# Sin_wave.net
KiCad netlist of a schematic drawn in Altium Designer
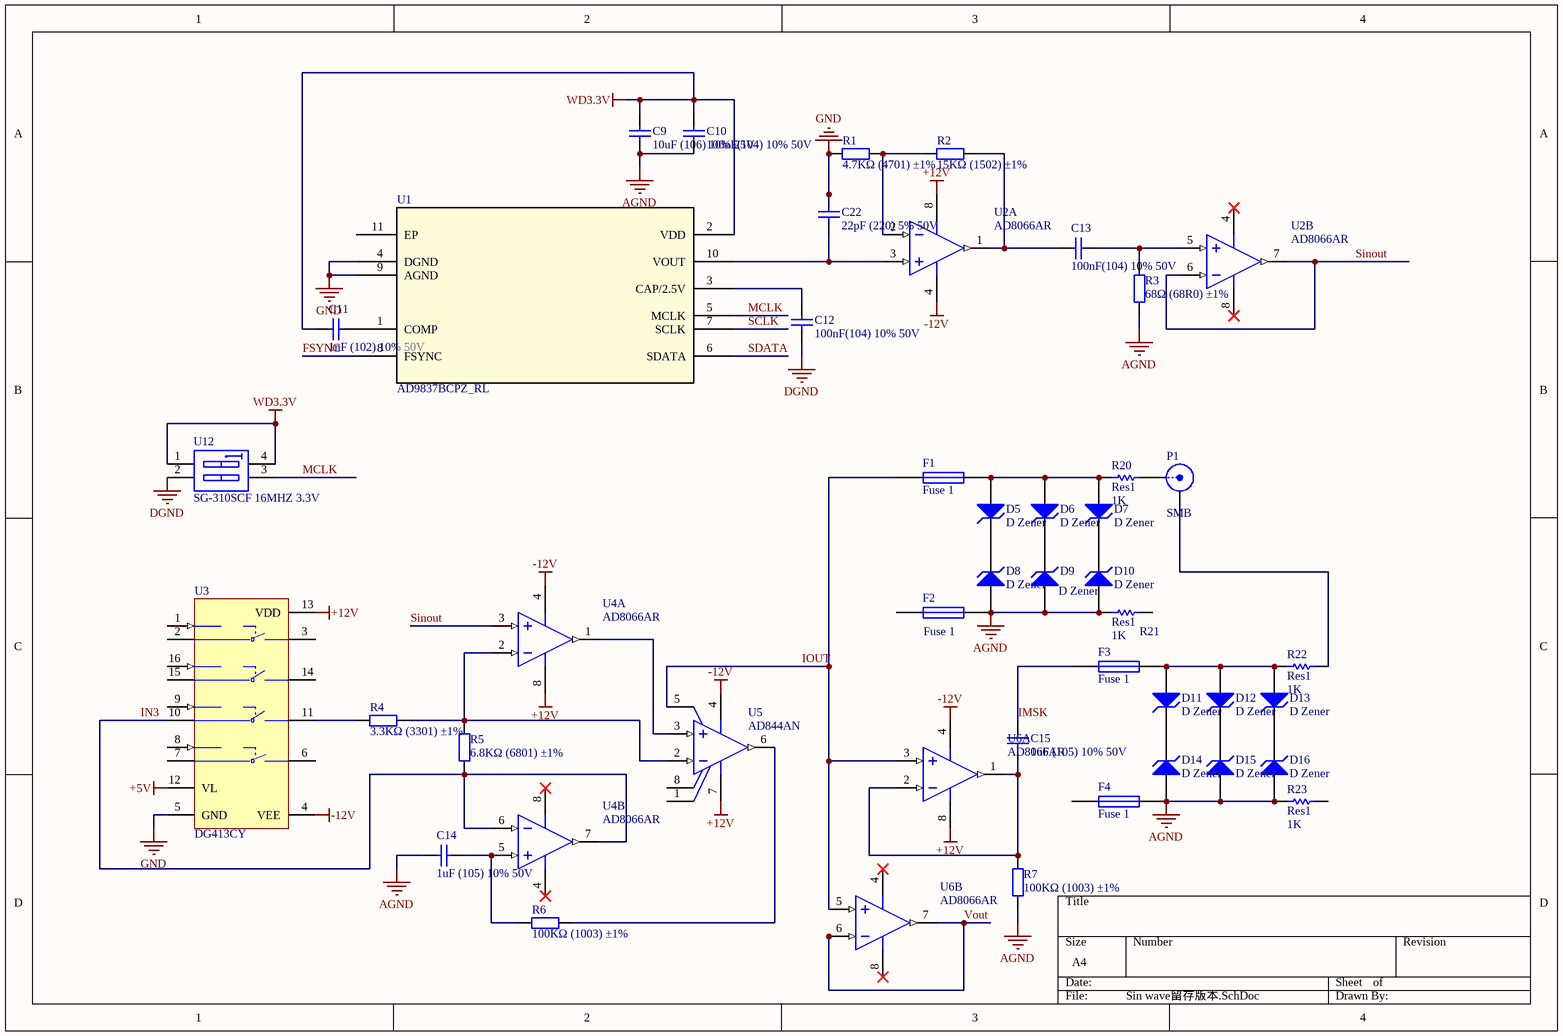
[diagram p0: Sin wave留存版本.SchDoc]

(export (version "E")
  (design (tool "Eeschema 10.0.6"))
  (components
    (comp (ref "C9")
      (value "10uF (106) 10% 25V")
      (footprint "LC-0805_C")
      (description "贴片电容")
      (libsource (lib "Miscellaneous Devices LC") (part "0805 10uF (106) 10% 25V"))
    )
    (comp (ref "C10")
      (value "100nF(104) 10% 50V")
      (footprint "LC-0805_C")
      (description "贴片电容")
      (libsource (lib "Miscellaneous Devices LC") (part "0805 100nF(104) 10% 50V"))
    )
    (comp (ref "C11")
      (value "1nF (102) 10% 50V")
      (footprint "LC-0805_C")
      (description "贴片电容")
      (libsource (lib "Miscellaneous Devices LC") (part "0805 1nF (102) 10% 50V"))
    )
    (comp (ref "C12")
      (value "100nF(104) 10% 50V")
      (footprint "LC-0805_C")
      (description "贴片电容")
      (libsource (lib "Miscellaneous Devices LC") (part "0805 100nF(104) 10% 50V"))
    )
    (comp (ref "C13")
      (value "100nF(104) 10% 50V")
      (footprint "LC-0805_C")
      (description "贴片电容")
      (libsource (lib "Miscellaneous Devices LC") (part "0805 100nF(104) 10% 50V"))
    )
    (comp (ref "C14")
      (value "1uF (105) 10% 50V")
      (footprint "LC-0805_C")
      (description "贴片电容")
      (libsource (lib "Miscellaneous Devices LC") (part "0805 1uF (105) 10% 50V"))
    )
    (comp (ref "C15")
      (value "1uF (105) 10% 50V")
      (footprint "LC-0805_C")
      (description "贴片电容")
      (libsource (lib "Miscellaneous Devices LC") (part "0805 1uF (105) 10% 50V"))
    )
    (comp (ref "C22")
      (value "22pF (220) 5% 50V")
      (footprint "LC-0805_C")
      (description "贴片电容")
      (libsource (lib "Miscellaneous Devices LC") (part "0805 22pF (220) 5% 50V"))
    )
    (comp (ref "D5")
      (value "D Zener")
      (footprint "DIODE-0.7")
      (description "Zener Diode")
      (fields (field (name "PUBLISHER") "Altium Limited"))
      (libsource (lib "Miscellaneous Devices") (part "D Zener"))
    )
    (comp (ref "D6")
      (value "D Zener")
      (footprint "DIODE-0.7")
      (description "Zener Diode")
      (fields (field (name "PUBLISHER") "Altium Limited"))
      (libsource (lib "Miscellaneous Devices") (part "D Zener"))
    )
    (comp (ref "D7")
      (value "D Zener")
      (footprint "DIODE-0.7")
      (description "Zener Diode")
      (fields (field (name "PUBLISHER") "Altium Limited"))
      (libsource (lib "Miscellaneous Devices") (part "D Zener"))
    )
    (comp (ref "D8")
      (value "D Zener")
      (footprint "DIODE-0.7")
      (description "Zener Diode")
      (fields (field (name "PUBLISHER") "Altium Limited"))
      (libsource (lib "Miscellaneous Devices") (part "D Zener"))
    )
    (comp (ref "D9")
      (value "D Zener")
      (footprint "DIODE-0.7")
      (description "Zener Diode")
      (fields (field (name "PUBLISHER") "Altium Limited"))
      (libsource (lib "Miscellaneous Devices") (part "D Zener"))
    )
    (comp (ref "D10")
      (value "D Zener")
      (footprint "DIODE-0.7")
      (description "Zener Diode")
      (fields (field (name "PUBLISHER") "Altium Limited"))
      (libsource (lib "Miscellaneous Devices") (part "D Zener"))
    )
    (comp (ref "D11")
      (value "D Zener")
      (footprint "DIODE-0.7")
      (description "Zener Diode")
      (fields (field (name "PUBLISHER") "Altium Limited"))
      (libsource (lib "Miscellaneous Devices") (part "D Zener"))
    )
    (comp (ref "D12")
      (value "D Zener")
      (footprint "DIODE-0.7")
      (description "Zener Diode")
      (fields (field (name "PUBLISHER") "Altium Limited"))
      (libsource (lib "Miscellaneous Devices") (part "D Zener"))
    )
    (comp (ref "D13")
      (value "D Zener")
      (footprint "DIODE-0.7")
      (description "Zener Diode")
      (fields (field (name "PUBLISHER") "Altium Limited"))
      (libsource (lib "Miscellaneous Devices") (part "D Zener"))
    )
    (comp (ref "D14")
      (value "D Zener")
      (footprint "DIODE-0.7")
      (description "Zener Diode")
      (fields (field (name "PUBLISHER") "Altium Limited"))
      (libsource (lib "Miscellaneous Devices") (part "D Zener"))
    )
    (comp (ref "D15")
      (value "D Zener")
      (footprint "DIODE-0.7")
      (description "Zener Diode")
      (fields (field (name "PUBLISHER") "Altium Limited"))
      (libsource (lib "Miscellaneous Devices") (part "D Zener"))
    )
    (comp (ref "D16")
      (value "D Zener")
      (footprint "DIODE-0.7")
      (description "Zener Diode")
      (fields (field (name "PUBLISHER") "Altium Limited"))
      (libsource (lib "Miscellaneous Devices") (part "D Zener"))
    )
    (comp (ref "F1")
      (value "Fuse 1")
      (footprint "PIN-W2/E2.8")
      (description "Fuse")
      (fields (field (name "PUBLISHER") "Altium Limited"))
      (libsource (lib "Miscellaneous Devices") (part "Fuse 1"))
    )
    (comp (ref "F2")
      (value "Fuse 1")
      (footprint "PIN-W2/E2.8")
      (description "Fuse")
      (fields (field (name "PUBLISHER") "Altium Limited"))
      (libsource (lib "Miscellaneous Devices") (part "Fuse 1"))
    )
    (comp (ref "F3")
      (value "Fuse 1")
      (footprint "PIN-W2/E2.8")
      (description "Fuse")
      (fields (field (name "PUBLISHER") "Altium Limited"))
      (libsource (lib "Miscellaneous Devices") (part "Fuse 1"))
    )
    (comp (ref "F4")
      (value "Fuse 1")
      (footprint "PIN-W2/E2.8")
      (description "Fuse")
      (fields (field (name "PUBLISHER") "Altium Limited"))
      (libsource (lib "Miscellaneous Devices") (part "Fuse 1"))
    )
    (comp (ref "P1")
      (value "SMB")
      (footprint "SMB_V-RJ45")
      (description "SMB Straight Connector")
      (fields (field (name "PUBLISHER") "Altium Limited"))
      (libsource (lib "Miscellaneous Connectors") (part "SMB"))
    )
    (comp (ref "R1")
      (value "4.7KΩ (4701) ±1%")
      (footprint "LC-0805_R")
      (description "贴片电阻")
      (libsource (lib "Miscellaneous Devices LC") (part "0805 4.7KΩ (4701) 1%"))
    )
    (comp (ref "R2")
      (value "15KΩ (1502) ±1%")
      (footprint "LC-0805_R")
      (description "贴片电阻")
      (libsource (lib "Miscellaneous Devices LC") (part "0805 15KΩ (1502) 1%"))
    )
    (comp (ref "R3")
      (value "68Ω (68R0) ±1%")
      (footprint "LC-0805_R")
      (description "贴片电阻")
      (libsource (lib "Miscellaneous Devices LC") (part "0805 68Ω (68R0) 1%"))
    )
    (comp (ref "R4")
      (value "3.3KΩ (3301) ±1%")
      (footprint "LC-0805_R")
      (description "贴片电阻")
      (libsource (lib "Miscellaneous Devices LC") (part "0805 3.3KΩ (3301) 1%"))
    )
    (comp (ref "R5")
      (value "6.8KΩ (6801) ±1%")
      (footprint "LC-0805_R")
      (description "贴片电阻")
      (libsource (lib "Miscellaneous Devices LC") (part "0805 6.8KΩ (6801) 1%"))
    )
    (comp (ref "R6")
      (value "100KΩ (1003) ±1%")
      (footprint "LC-0805_R")
      (description "贴片电阻")
      (libsource (lib "Miscellaneous Devices LC") (part "0805 100KΩ (1003) 1%"))
    )
    (comp (ref "R7")
      (value "100KΩ (1003) ±1%")
      (footprint "LC-0805_R")
      (description "贴片电阻")
      (libsource (lib "") (part "0805 100KΩ (1003) 1%_1"))
    )
    (comp (ref "R20")
      (value "Res1")
      (footprint "AXIAL-0.3")
      (description "Resistor")
      (fields (field (name "ALTIUM_VALUE") "1K") (field (name "PUBLISHER") "Altium Limited"))
      (libsource (lib "Miscellaneous Devices") (part "Res1"))
    )
    (comp (ref "R21")
      (value "Res1")
      (footprint "AXIAL-0.3")
      (description "Resistor")
      (fields (field (name "ALTIUM_VALUE") "1K") (field (name "PUBLISHER") "Altium Limited"))
      (libsource (lib "Miscellaneous Devices") (part "Res1"))
    )
    (comp (ref "R22")
      (value "Res1")
      (footprint "AXIAL-0.3")
      (description "Resistor")
      (fields (field (name "ALTIUM_VALUE") "1K") (field (name "PUBLISHER") "Altium Limited"))
      (libsource (lib "Miscellaneous Devices") (part "Res1"))
    )
    (comp (ref "R23")
      (value "Res1")
      (footprint "AXIAL-0.3")
      (description "Resistor")
      (fields (field (name "ALTIUM_VALUE") "1K") (field (name "PUBLISHER") "Altium Limited"))
      (libsource (lib "Miscellaneous Devices") (part "Res1"))
    )
    (comp (ref "U1")
      (value "AD9837BCPZ_RL")
      (footprint "CP_10_9")
      (description "Imported")
      (libsource (lib "AD9837") (part "AD9837BCPZ_RL"))
    )
    (comp (ref "U2")
      (value "AD8066AR")
      (footprint "ADI-R-8_N")
      (fields (field (name "GENERIC PART NUMBER") "AD8066") (field (name "MANUFACTURER") "Analog Devices"))
      (libsource (lib "Analog Devices Operational Amplifiers") (part "AD8066AR"))
    )
    (comp (ref "U3")
      (value "DG413CY")
      (footprint "NSO16_N")
      (description "Improved, Quad, SPST Analog Switches")
      (fields (field (name "PUBLISHER") "Altium Limited"))
      (libsource (lib "Maxim Logic Switch") (part "DG413CY"))
    )
    (comp (ref "U4")
      (value "AD8066AR")
      (footprint "ADI-R-8_N")
      (fields (field (name "GENERIC PART NUMBER") "AD8066") (field (name "MANUFACTURER") "Analog Devices"))
      (libsource (lib "Analog Devices Operational Amplifiers") (part "AD8066AR"))
    )
    (comp (ref "U5")
      (value "AD844AN")
      (footprint "ADI-N-8")
      (fields (field (name "GENERIC PART NUMBER") "AD844") (field (name "MANUFACTURER") "Analog Devices"))
      (libsource (lib "Analog Devices Operational Amplifiers") (part "AD844AN"))
    )
    (comp (ref "U6")
      (value "AD8066AR")
      (footprint "ADI-R-8_N")
      (fields (field (name "GENERIC PART NUMBER") "AD8066") (field (name "MANUFACTURER") "Analog Devices"))
      (libsource (lib "Analog Devices Operational Amplifiers") (part "AD8066AR"))
    )
    (comp (ref "U12")
      (value "SG-310SCF 16MHZ 3.3V")
      (footprint "LC-SMD-7050_4P")
      (description "DIP Switch, 2 Position, SPST")
      (fields (field (name "PUBLISHER") "Altium Limited"))
      (libsource (lib "Miscellaneous Devices") (part "SW DIP-2"))
    )
  )
  (nets
    (net (code "1") (name "+5V") (class "Default")
      (node (ref "U3") (pin "12") (pinfunction "VL_12") (pintype "power_in"))
    )
    (net (code "2") (name "+12V") (class "Default")
      (node (ref "U2") (pin "8") (pinfunction "+VS_8") (pintype "power_in"))
      (node (ref "U3") (pin "13") (pinfunction "VDD_13") (pintype "power_in"))
      (node (ref "U4") (pin "8") (pinfunction "+VS_8") (pintype "power_in"))
      (node (ref "U5") (pin "7") (pinfunction "+VS_7") (pintype "power_in"))
      (node (ref "U6") (pin "8") (pinfunction "+VS_8") (pintype "power_in"))
    )
    (net (code "3") (name "-12V") (class "Default")
      (node (ref "U2") (pin "4") (pinfunction "-VS_4") (pintype "power_in"))
      (node (ref "U3") (pin "4") (pinfunction "VEE_4") (pintype "power_in"))
      (node (ref "U4") (pin "4") (pinfunction "-VS_4") (pintype "power_in"))
      (node (ref "U5") (pin "4") (pinfunction "-VS_4") (pintype "power_in"))
      (node (ref "U6") (pin "4") (pinfunction "-VS_4") (pintype "power_in"))
    )
    (net (code "4") (name "/FSYNC") (class "Default")
      (node (ref "U1") (pin "8") (pinfunction "FSYNC_8") (pintype "passive"))
    )
    (net (code "5") (name "/IMSK") (class "Default")
      (node (ref "C15") (pin "2") (pinfunction "2_2") (pintype "passive"))
      (node (ref "F3") (pin "1") (pinfunction "1_1") (pintype "passive"))
    )
    (net (code "6") (name "/IN3") (class "Default")
      (node (ref "R5") (pin "1") (pinfunction "1_1") (pintype "passive"))
      (node (ref "U3") (pin "10") (pinfunction "D3_10") (pintype "passive"))
      (node (ref "U4") (pin "6") (pinfunction "-IN_2_6") (pintype "input"))
      (node (ref "U4") (pin "7") (pinfunction "VOUT_2_7") (pintype "output"))
    )
    (net (code "7") (name "/IOUT") (class "Default")
      (node (ref "F1") (pin "1") (pinfunction "1_1") (pintype "passive"))
      (node (ref "U5") (pin "5") (pinfunction "TZ_5") (pintype "passive"))
      (node (ref "U6") (pin "3") (pinfunction "+IN_1_3") (pintype "input"))
      (node (ref "U6") (pin "5") (pinfunction "+IN_2_5") (pintype "input"))
    )
    (net (code "8") (name "/MCLK") (class "Default")
      (node (ref "U1") (pin "5") (pinfunction "MCLK_5") (pintype "passive"))
      (node (ref "U12") (pin "3") (pinfunction "B2_3") (pintype "passive"))
    )
    (net (code "9") (name "/SCLK") (class "Default")
      (node (ref "U1") (pin "7") (pinfunction "SCLK_7") (pintype "passive"))
    )
    (net (code "10") (name "/SDATA") (class "Default")
      (node (ref "U1") (pin "6") (pinfunction "SDATA_6") (pintype "passive"))
    )
    (net (code "11") (name "/Sinout") (class "Default")
      (node (ref "U2") (pin "6") (pinfunction "-IN_2_6") (pintype "input"))
      (node (ref "U2") (pin "7") (pinfunction "VOUT_2_7") (pintype "output"))
      (node (ref "U4") (pin "3") (pinfunction "+IN_1_3") (pintype "input"))
    )
    (net (code "12") (name "/Vout") (class "Default")
      (node (ref "U6") (pin "6") (pinfunction "-IN_2_6") (pintype "input"))
      (node (ref "U6") (pin "7") (pinfunction "VOUT_2_7") (pintype "output"))
    )
    (net (code "13") (name "AGND") (class "Default")
      (node (ref "C10") (pin "1") (pinfunction "1_1") (pintype "passive"))
      (node (ref "C14") (pin "1") (pinfunction "1_1") (pintype "passive"))
      (node (ref "C9") (pin "1") (pinfunction "1_1") (pintype "passive"))
      (node (ref "D10") (pin "1") (pinfunction "A_1") (pintype "passive"))
      (node (ref "D14") (pin "1") (pinfunction "A_1") (pintype "passive"))
      (node (ref "D15") (pin "1") (pinfunction "A_1") (pintype "passive"))
      (node (ref "D16") (pin "1") (pinfunction "A_1") (pintype "passive"))
      (node (ref "D8") (pin "1") (pinfunction "A_1") (pintype "passive"))
      (node (ref "D9") (pin "1") (pinfunction "A_1") (pintype "passive"))
      (node (ref "F2") (pin "2") (pinfunction "2_2") (pintype "passive"))
      (node (ref "F4") (pin "2") (pinfunction "2_2") (pintype "passive"))
      (node (ref "R21") (pin "1") (pinfunction "1_1") (pintype "passive"))
      (node (ref "R23") (pin "1") (pinfunction "1_1") (pintype "passive"))
      (node (ref "R3") (pin "1") (pinfunction "1_1") (pintype "passive"))
      (node (ref "R7") (pin "1") (pinfunction "1_1") (pintype "passive"))
    )
    (net (code "14") (name "DGND") (class "Default")
      (node (ref "C12") (pin "1") (pinfunction "1_1") (pintype "passive"))
      (node (ref "U12") (pin "2") (pinfunction "A2_2") (pintype "passive"))
    )
    (net (code "15") (name "GND") (class "Default")
      (node (ref "C22") (pin "2") (pinfunction "2_2") (pintype "passive"))
      (node (ref "R1") (pin "1") (pinfunction "1_1") (pintype "passive"))
      (node (ref "U1") (pin "4") (pinfunction "DGND_4") (pintype "passive"))
      (node (ref "U1") (pin "9") (pinfunction "AGND_9") (pintype "passive"))
      (node (ref "U3") (pin "5") (pinfunction "GND_5") (pintype "power_in"))
    )
    (net (code "16") (name "Net-(D5-A)") (class "Default")
      (node (ref "D5") (pin "1") (pinfunction "A_1") (pintype "passive"))
      (node (ref "D6") (pin "1") (pinfunction "A_1") (pintype "passive"))
      (node (ref "D7") (pin "1") (pinfunction "A_1") (pintype "passive"))
      (node (ref "F1") (pin "2") (pinfunction "2_2") (pintype "passive"))
      (node (ref "R20") (pin "1") (pinfunction "1_1") (pintype "passive"))
    )
    (net (code "17") (name "Net-(D5-K)") (class "Default")
      (node (ref "D5") (pin "2") (pinfunction "K_2") (pintype "passive"))
      (node (ref "D8") (pin "2") (pinfunction "K_2") (pintype "passive"))
    )
    (net (code "18") (name "Net-(D6-K)") (class "Default")
      (node (ref "D6") (pin "2") (pinfunction "K_2") (pintype "passive"))
      (node (ref "D9") (pin "2") (pinfunction "K_2") (pintype "passive"))
    )
    (net (code "19") (name "Net-(D10-K)") (class "Default")
      (node (ref "D10") (pin "2") (pinfunction "K_2") (pintype "passive"))
      (node (ref "D7") (pin "2") (pinfunction "K_2") (pintype "passive"))
    )
    (net (code "20") (name "Net-(D11-A)") (class "Default")
      (node (ref "D11") (pin "1") (pinfunction "A_1") (pintype "passive"))
      (node (ref "D12") (pin "1") (pinfunction "A_1") (pintype "passive"))
      (node (ref "D13") (pin "1") (pinfunction "A_1") (pintype "passive"))
      (node (ref "F3") (pin "2") (pinfunction "2_2") (pintype "passive"))
      (node (ref "R22") (pin "1") (pinfunction "1_1") (pintype "passive"))
    )
    (net (code "21") (name "Net-(D11-K)") (class "Default")
      (node (ref "D11") (pin "2") (pinfunction "K_2") (pintype "passive"))
      (node (ref "D14") (pin "2") (pinfunction "K_2") (pintype "passive"))
    )
    (net (code "22") (name "Net-(D12-K)") (class "Default")
      (node (ref "D12") (pin "2") (pinfunction "K_2") (pintype "passive"))
      (node (ref "D15") (pin "2") (pinfunction "K_2") (pintype "passive"))
    )
    (net (code "23") (name "Net-(D13-K)") (class "Default")
      (node (ref "D13") (pin "2") (pinfunction "K_2") (pintype "passive"))
      (node (ref "D16") (pin "2") (pinfunction "K_2") (pintype "passive"))
    )
    (net (code "24") (name "Net-(P1-X)") (class "Default")
      (node (ref "P1") (pin "1") (pinfunction "X_1") (pintype "passive"))
      (node (ref "R20") (pin "2") (pinfunction "2_2") (pintype "passive"))
    )
    (net (code "25") (name "Net-(P1-Y)") (class "Default")
      (node (ref "P1") (pin "2") (pinfunction "Y_2") (pintype "passive"))
      (node (ref "R22") (pin "2") (pinfunction "2_2") (pintype "passive"))
    )
    (net (code "26") (name "Net-(U1-CAP{slash}2.5V)") (class "Default")
      (node (ref "C12") (pin "2") (pinfunction "2_2") (pintype "passive"))
      (node (ref "U1") (pin "3") (pinfunction "CAP/2.5V_3") (pintype "passive"))
    )
    (net (code "27") (name "Net-(U1-COMP)") (class "Default")
      (node (ref "C11") (pin "2") (pinfunction "2_2") (pintype "passive"))
      (node (ref "U1") (pin "1") (pinfunction "COMP_1") (pintype "passive"))
    )
    (net (code "28") (name "Net-(U1-VOUT)") (class "Default")
      (node (ref "C22") (pin "1") (pinfunction "1_1") (pintype "passive"))
      (node (ref "U1") (pin "10") (pinfunction "VOUT_10") (pintype "passive"))
      (node (ref "U2") (pin "3") (pinfunction "+IN_1_3") (pintype "input"))
    )
    (net (code "29") (name "Net-(U2A--IN_1)") (class "Default")
      (node (ref "R1") (pin "2") (pinfunction "2_2") (pintype "passive"))
      (node (ref "R2") (pin "1") (pinfunction "1_1") (pintype "passive"))
      (node (ref "U2") (pin "2") (pinfunction "-IN_1_2") (pintype "input"))
    )
    (net (code "30") (name "Net-(U2A-VOUT_1)") (class "Default")
      (node (ref "C13") (pin "1") (pinfunction "1_1") (pintype "passive"))
      (node (ref "R2") (pin "2") (pinfunction "2_2") (pintype "passive"))
      (node (ref "U2") (pin "1") (pinfunction "VOUT_1_1") (pintype "output"))
    )
    (net (code "31") (name "Net-(U2B-+IN_2)") (class "Default")
      (node (ref "C13") (pin "2") (pinfunction "2_2") (pintype "passive"))
      (node (ref "R3") (pin "2") (pinfunction "2_2") (pintype "passive"))
      (node (ref "U2") (pin "5") (pinfunction "+IN_2_5") (pintype "input"))
    )
    (net (code "32") (name "Net-(U3-S3)") (class "Default")
      (node (ref "R4") (pin "1") (pinfunction "1_1") (pintype "passive"))
      (node (ref "U3") (pin "11") (pinfunction "S3_11") (pintype "passive"))
    )
    (net (code "33") (name "Net-(U4A--IN_1)") (class "Default")
      (node (ref "R4") (pin "2") (pinfunction "2_2") (pintype "passive"))
      (node (ref "R5") (pin "2") (pinfunction "2_2") (pintype "passive"))
      (node (ref "U4") (pin "2") (pinfunction "-IN_1_2") (pintype "input"))
      (node (ref "U5") (pin "2") (pinfunction "-IN_2") (pintype "input"))
    )
    (net (code "34") (name "Net-(U4A-VOUT_1)") (class "Default")
      (node (ref "U4") (pin "1") (pinfunction "VOUT_1_1") (pintype "output"))
      (node (ref "U5") (pin "3") (pinfunction "+IN_3") (pintype "input"))
    )
    (net (code "35") (name "Net-(U4B-+IN_2)") (class "Default")
      (node (ref "C14") (pin "2") (pinfunction "2_2") (pintype "passive"))
      (node (ref "R6") (pin "1") (pinfunction "1_1") (pintype "passive"))
      (node (ref "U4") (pin "5") (pinfunction "+IN_2_5") (pintype "input"))
    )
    (net (code "36") (name "Net-(U5-OUTPUT)") (class "Default")
      (node (ref "R6") (pin "2") (pinfunction "2_2") (pintype "passive"))
      (node (ref "U5") (pin "6") (pinfunction "OUTPUT_6") (pintype "output"))
    )
    (net (code "37") (name "Net-(U6A--IN_1)") (class "Default")
      (node (ref "C15") (pin "1") (pinfunction "1_1") (pintype "passive"))
      (node (ref "R7") (pin "2") (pinfunction "2_2") (pintype "passive"))
      (node (ref "U6") (pin "1") (pinfunction "VOUT_1_1") (pintype "output"))
      (node (ref "U6") (pin "2") (pinfunction "-IN_1_2") (pintype "input"))
    )
    (net (code "38") (name "WD3.3V") (class "Default")
      (node (ref "C10") (pin "2") (pinfunction "2_2") (pintype "passive"))
      (node (ref "C11") (pin "1") (pinfunction "1_1") (pintype "passive"))
      (node (ref "C9") (pin "2") (pinfunction "2_2") (pintype "passive"))
      (node (ref "U1") (pin "2") (pinfunction "VDD_2") (pintype "passive"))
      (node (ref "U12") (pin "1") (pinfunction "A1_1") (pintype "passive"))
      (node (ref "U12") (pin "4") (pinfunction "B1_4") (pintype "passive"))
    )
    (net (code "39") (name "unconnected-(F2-Pad1)") (class "Default")
      (node (ref "F2") (pin "1") (pinfunction "1_1") (pintype "passive"))
    )
    (net (code "40") (name "unconnected-(F4-Pad1)") (class "Default")
      (node (ref "F4") (pin "1") (pinfunction "1_1") (pintype "passive"))
    )
    (net (code "41") (name "unconnected-(R21-Pad2)") (class "Default")
      (node (ref "R21") (pin "2") (pinfunction "2_2") (pintype "passive"))
    )
    (net (code "42") (name "unconnected-(R23-Pad2)") (class "Default")
      (node (ref "R23") (pin "2") (pinfunction "2_2") (pintype "passive"))
    )
    (net (code "43") (name "unconnected-(U1-EP-Pad11)") (class "Default")
      (node (ref "U1") (pin "11") (pinfunction "EP_11") (pintype "passive"))
    )
    (net (code "44") (name "unconnected-(U2B-+VS-Pad8)") (class "Default")
      (node (ref "U2") (pin "8") (pinfunction "+VS_8") (pintype "power_in+no_connect"))
    )
    (net (code "45") (name "unconnected-(U2B--VS-Pad4)") (class "Default")
      (node (ref "U2") (pin "4") (pinfunction "-VS_4") (pintype "power_in+no_connect"))
    )
    (net (code "46") (name "unconnected-(U3-D1-Pad2)") (class "Default")
      (node (ref "U3") (pin "2") (pinfunction "D1_2") (pintype "passive"))
    )
    (net (code "47") (name "unconnected-(U3-D2-Pad15)") (class "Default")
      (node (ref "U3") (pin "15") (pinfunction "D2_15") (pintype "passive"))
    )
    (net (code "48") (name "unconnected-(U3-D4-Pad7)") (class "Default")
      (node (ref "U3") (pin "7") (pinfunction "D4_7") (pintype "passive"))
    )
    (net (code "49") (name "unconnected-(U3-IN1-Pad1)") (class "Default")
      (node (ref "U3") (pin "1") (pinfunction "IN1_1") (pintype "input"))
    )
    (net (code "50") (name "unconnected-(U3-IN2-Pad16)") (class "Default")
      (node (ref "U3") (pin "16") (pinfunction "IN2_16") (pintype "input"))
    )
    (net (code "51") (name "unconnected-(U3-IN3-Pad9)") (class "Default")
      (node (ref "U3") (pin "9") (pinfunction "IN3_9") (pintype "input"))
    )
    (net (code "52") (name "unconnected-(U3-IN_4-Pad8)") (class "Default")
      (node (ref "U3") (pin "8") (pinfunction "IN_4_8") (pintype "input"))
    )
    (net (code "53") (name "unconnected-(U3-S1-Pad3)") (class "Default")
      (node (ref "U3") (pin "3") (pinfunction "S1_3") (pintype "passive"))
    )
    (net (code "54") (name "unconnected-(U3-S2-Pad14)") (class "Default")
      (node (ref "U3") (pin "14") (pinfunction "S2_14") (pintype "passive"))
    )
    (net (code "55") (name "unconnected-(U3-S4-Pad6)") (class "Default")
      (node (ref "U3") (pin "6") (pinfunction "S4_6") (pintype "passive"))
    )
    (net (code "56") (name "unconnected-(U4B-+VS-Pad8)") (class "Default")
      (node (ref "U4") (pin "8") (pinfunction "+VS_8") (pintype "power_in+no_connect"))
    )
    (net (code "57") (name "unconnected-(U4B--VS-Pad4)") (class "Default")
      (node (ref "U4") (pin "4") (pinfunction "-VS_4") (pintype "power_in+no_connect"))
    )
    (net (code "58") (name "unconnected-(U5-NULL-Pad1)") (class "Default")
      (node (ref "U5") (pin "1") (pinfunction "NULL_1") (pintype "passive"))
    )
    (net (code "59") (name "unconnected-(U5-NULL-Pad8)") (class "Default")
      (node (ref "U5") (pin "8") (pinfunction "NULL_8") (pintype "passive"))
    )
    (net (code "60") (name "unconnected-(U6B-+VS-Pad8)") (class "Default")
      (node (ref "U6") (pin "8") (pinfunction "+VS_8") (pintype "power_in+no_connect"))
    )
    (net (code "61") (name "unconnected-(U6B--VS-Pad4)") (class "Default")
      (node (ref "U6") (pin "4") (pinfunction "-VS_4") (pintype "power_in+no_connect"))
    )
  )
)
